# Shema.net
KiCad netlist of a schematic drawn in Altium Designer
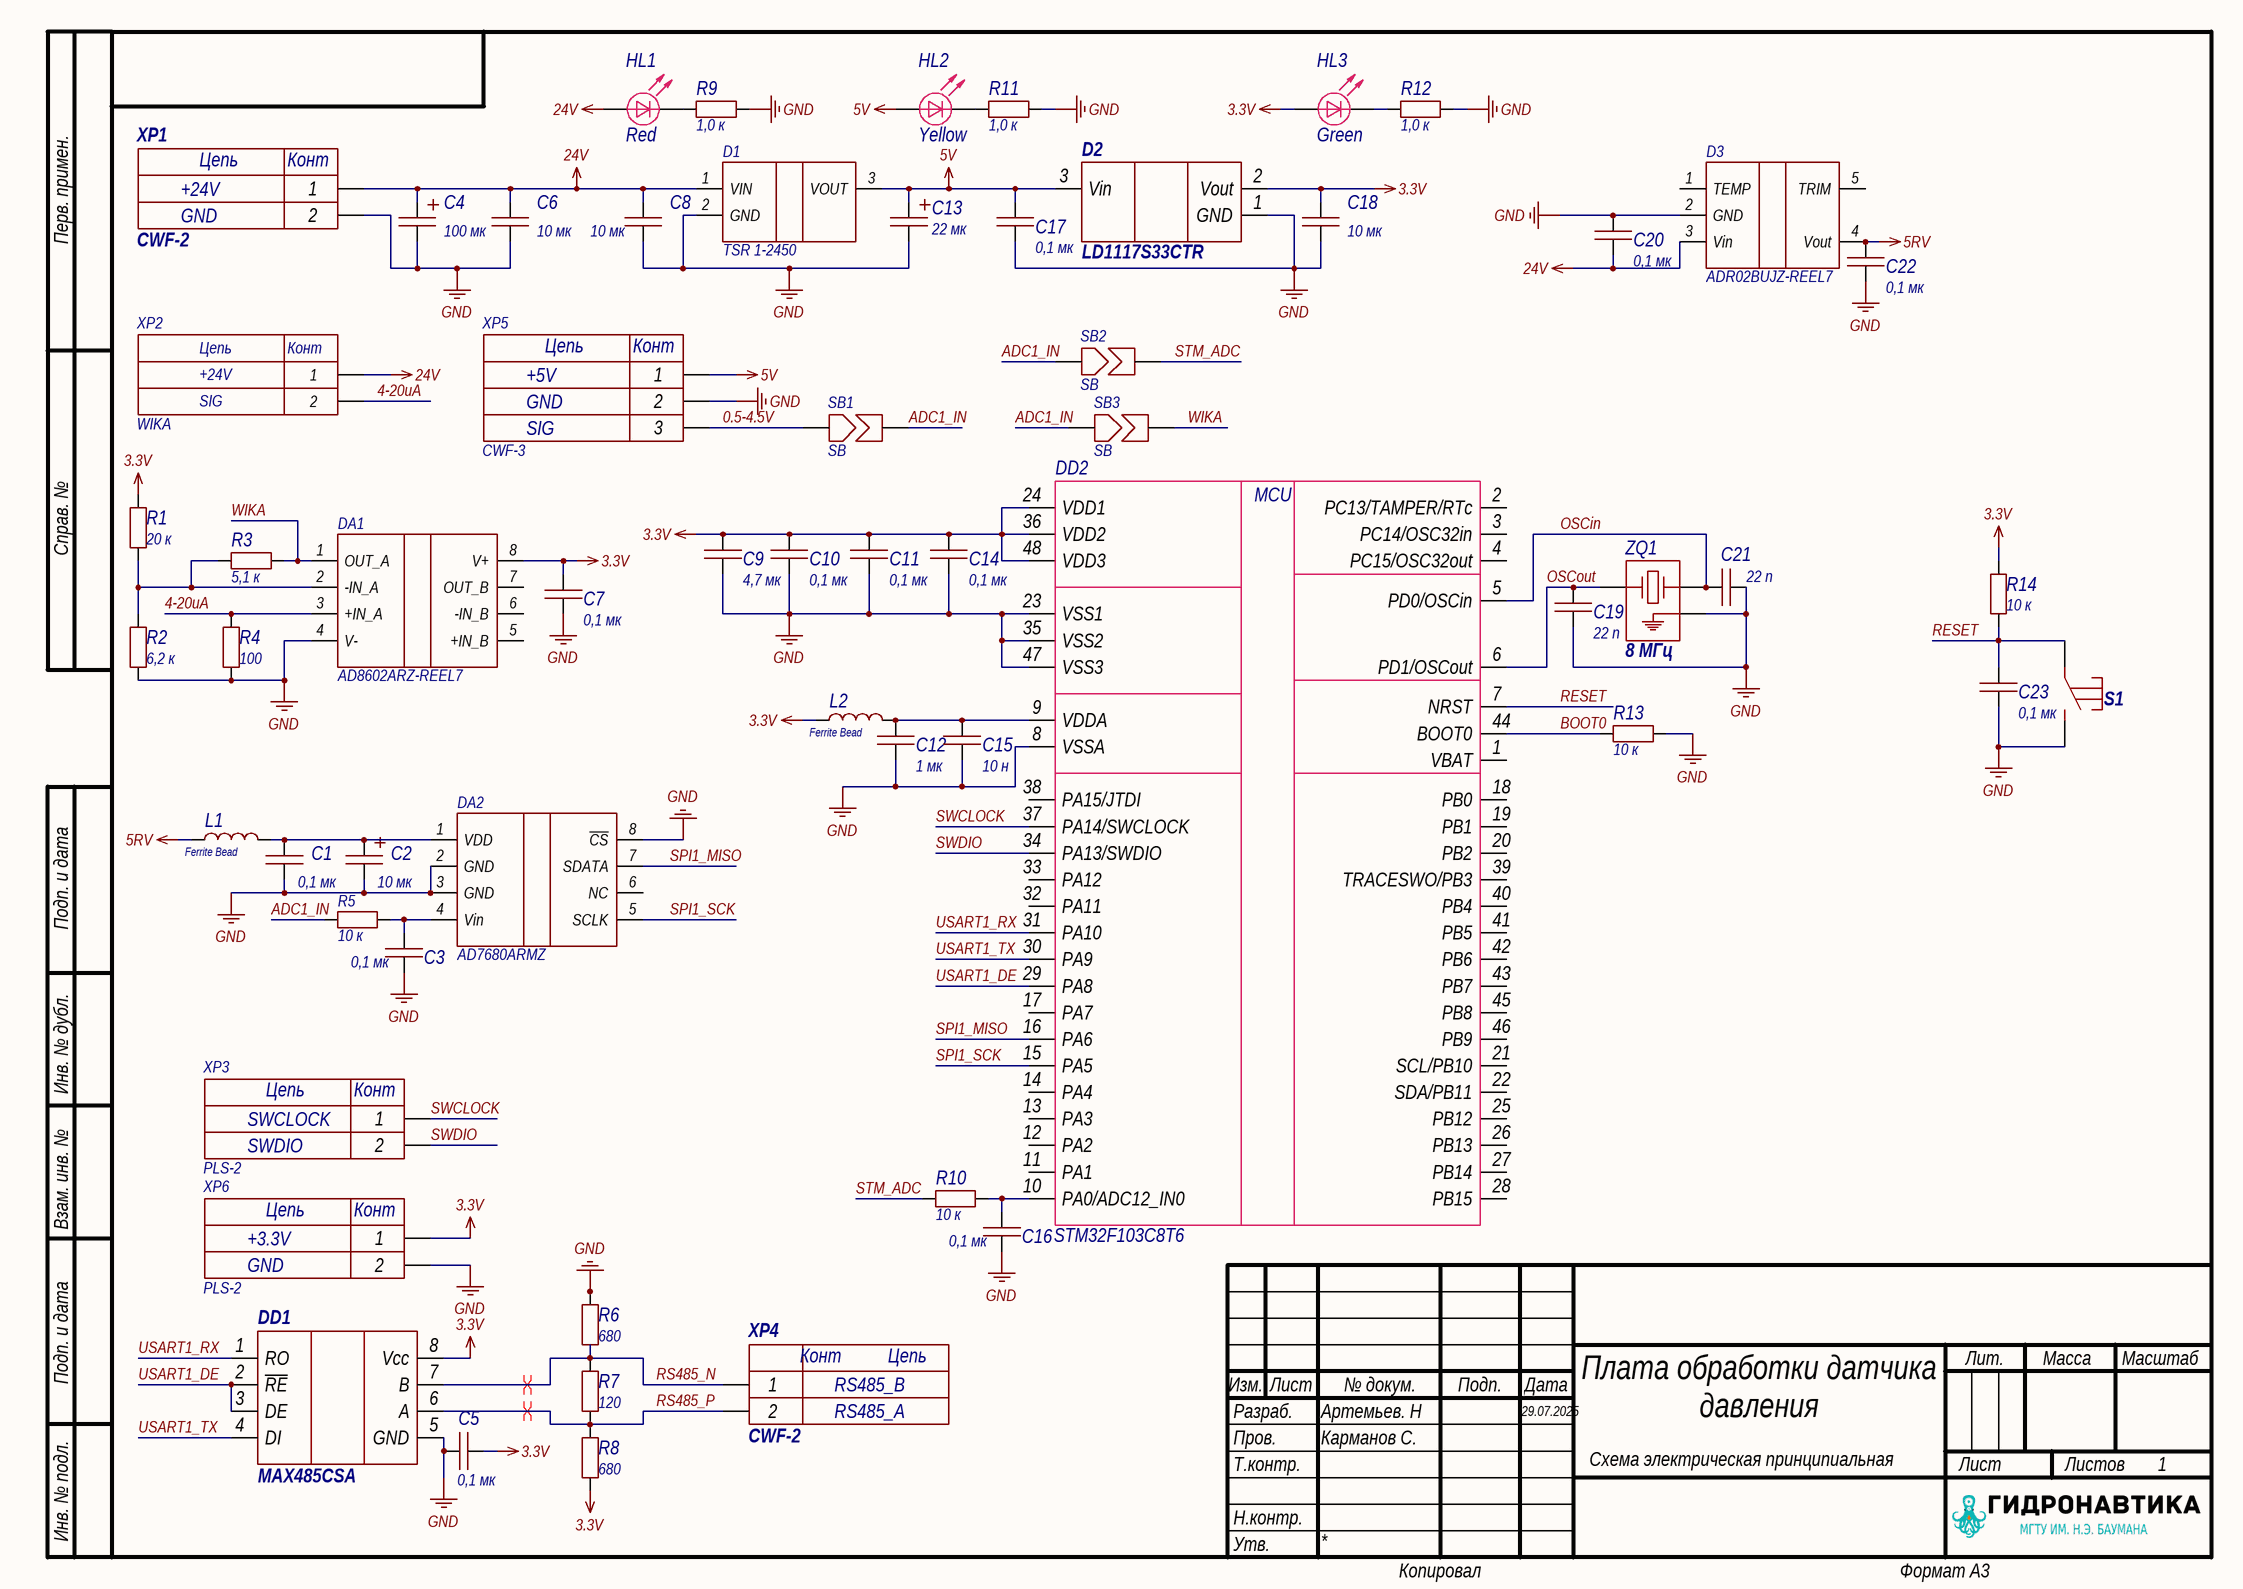
[diagram p0: Shema.SchDoc]

(export (version "E")
  (design (tool "Eeschema 10.0.6"))
  (components
    (comp (ref "C1")
      (value "0,1 мк")
      (footprint "0603C")
      (description "Конденсатор")
      (fields (field (name "PART NUMBER") "Capacitor_0,1u_10_50V_X7R_0603C") (field (name "TOLERANCE") "0,1"))
      (libsource (lib "Hydrolib") (part "Capacitor"))
    )
    (comp (ref "C2")
      (value "10 мк")
      (footprint "TC_A")
      (description "Танталовый конденсатор")
      (fields (field (name "PART NUMBER") "Capacitor_10u_10_50V_TC_A") (field (name "TOLERANCE") "0,1"))
      (libsource (lib "Hydrolib") (part "Capacitor_polar"))
    )
    (comp (ref "C3")
      (value "0,1 мк")
      (footprint "0603C")
      (description "Конденсатор")
      (fields (field (name "PART NUMBER") "Capacitor_0,1u_10_50V_X7R_0603C") (field (name "TOLERANCE") "0,1"))
      (libsource (lib "Hydrolib") (part "Capacitor"))
    )
    (comp (ref "C4")
      (value "100 мк")
      (footprint "TC_A")
      (description "Танталовый конденсатор")
      (fields (field (name "PART NUMBER") "Capacitor_100u_10_50V_TC_A") (field (name "TOLERANCE") "0,1"))
      (libsource (lib "Hydrolib") (part "Capacitor_polar"))
    )
    (comp (ref "C5")
      (value "0,1 мк")
      (footprint "0603C")
      (description "Конденсатор")
      (fields (field (name "PART NUMBER") "Capacitor_0,1u_10_50V_X7R_0603C") (field (name "TOLERANCE") "0,1"))
      (libsource (lib "Hydrolib") (part "Capacitor"))
    )
    (comp (ref "C6")
      (value "10 мк")
      (footprint "1210C")
      (description "Конденсатор")
      (fields (field (name "PART NUMBER") "Capacitor_10u_10_35V_X7R_1210C") (field (name "TOLERANCE") "0,1"))
      (libsource (lib "Hydrolib") (part "Capacitor"))
    )
    (comp (ref "C7")
      (value "0,1 мк")
      (footprint "0603C")
      (description "Конденсатор")
      (fields (field (name "PART NUMBER") "Capacitor_0,1u_10_50V_X7R_0603C") (field (name "TOLERANCE") "0,1"))
      (libsource (lib "Hydrolib") (part "Capacitor"))
    )
    (comp (ref "C8")
      (value "10 мк")
      (footprint "1210C")
      (description "Конденсатор")
      (fields (field (name "PART NUMBER") "Capacitor_10u_10_35V_X7R_1210C") (field (name "TOLERANCE") "0,1"))
      (libsource (lib "Hydrolib") (part "Capacitor"))
    )
    (comp (ref "C9")
      (value "4,7 мк")
      (footprint "1206C")
      (description "Конденсатор")
      (fields (field (name "PART NUMBER") "Capacitor_4,7u_10_50V_X7R_1206C") (field (name "TOLERANCE") "0,1"))
      (libsource (lib "Hydrolib") (part "Capacitor"))
    )
    (comp (ref "C10")
      (value "0,1 мк")
      (footprint "0603C")
      (description "Конденсатор")
      (fields (field (name "PART NUMBER") "Capacitor_0,1u_10_50V_X7R_0603C") (field (name "TOLERANCE") "0,1"))
      (libsource (lib "Hydrolib") (part "Capacitor"))
    )
    (comp (ref "C11")
      (value "0,1 мк")
      (footprint "0603C")
      (description "Конденсатор")
      (fields (field (name "PART NUMBER") "Capacitor_0,1u_10_50V_X7R_0603C") (field (name "TOLERANCE") "0,1"))
      (libsource (lib "Hydrolib") (part "Capacitor"))
    )
    (comp (ref "C12")
      (value "1 мк")
      (footprint "0603C")
      (description "Конденсатор")
      (fields (field (name "PART NUMBER") "Capacitor_1u_10_50V_X7R_0603C") (field (name "TOLERANCE") "0,1"))
      (libsource (lib "Hydrolib") (part "Capacitor"))
    )
    (comp (ref "C13")
      (value "22 мк")
      (footprint "TC_A")
      (description "Танталовый конденсатор")
      (fields (field (name "PART NUMBER") "Capacitor_22u_10_50V_TC_A") (field (name "TOLERANCE") "0,1"))
      (libsource (lib "Hydrolib") (part "Capacitor_polar"))
    )
    (comp (ref "C14")
      (value "0,1 мк")
      (footprint "0603C")
      (description "Конденсатор")
      (fields (field (name "PART NUMBER") "Capacitor_0,1u_10_50V_X7R_0603C") (field (name "TOLERANCE") "0,1"))
      (libsource (lib "Hydrolib") (part "Capacitor"))
    )
    (comp (ref "C15")
      (value "10 н")
      (footprint "0603C")
      (description "Конденсатор")
      (fields (field (name "PART NUMBER") "Capacitor_10n_10_50V_X7R_0603C") (field (name "TOLERANCE") "0,1"))
      (libsource (lib "Hydrolib") (part "Capacitor"))
    )
    (comp (ref "C16")
      (value "0,1 мк")
      (footprint "0603C")
      (description "Конденсатор")
      (fields (field (name "PART NUMBER") "Capacitor_0,1u_10_50V_X7R_0603C") (field (name "TOLERANCE") "0,1"))
      (libsource (lib "Hydrolib") (part "Capacitor"))
    )
    (comp (ref "C17")
      (value "0,1 мк")
      (footprint "0603C")
      (description "Конденсатор")
      (fields (field (name "PART NUMBER") "Capacitor_0,1u_10_50V_X7R_0603C") (field (name "TOLERANCE") "0,1"))
      (libsource (lib "Hydrolib") (part "Capacitor"))
    )
    (comp (ref "C18")
      (value "10 мк")
      (footprint "1210C")
      (description "Конденсатор")
      (fields (field (name "PART NUMBER") "Capacitor_10u_10_35V_X7R_1210C") (field (name "TOLERANCE") "0,1"))
      (libsource (lib "Hydrolib") (part "Capacitor"))
    )
    (comp (ref "C19")
      (value "22 п")
      (footprint "0603C")
      (description "Конденсатор")
      (fields (field (name "PART NUMBER") "Capacitor_22p_5_50V_X7R_0603C") (field (name "TOLERANCE") "0,05"))
      (libsource (lib "Hydrolib") (part "Capacitor"))
    )
    (comp (ref "C20")
      (value "0,1 мк")
      (footprint "0603C")
      (description "Конденсатор")
      (fields (field (name "PART NUMBER") "Capacitor_0,1u_10_50V_X7R_0603C") (field (name "TOLERANCE") "0,1"))
      (libsource (lib "Hydrolib") (part "Capacitor"))
    )
    (comp (ref "C21")
      (value "22 п")
      (footprint "0603C")
      (description "Конденсатор")
      (fields (field (name "PART NUMBER") "Capacitor_22p_5_50V_X7R_0603C") (field (name "TOLERANCE") "0,05"))
      (libsource (lib "Hydrolib") (part "Capacitor"))
    )
    (comp (ref "C22")
      (value "0,1 мк")
      (footprint "0603C")
      (description "Конденсатор")
      (fields (field (name "PART NUMBER") "Capacitor_0,1u_10_50V_X7R_0603C") (field (name "TOLERANCE") "0,1"))
      (libsource (lib "Hydrolib") (part "Capacitor"))
    )
    (comp (ref "C23")
      (value "0,1 мк")
      (footprint "0603C")
      (description "Конденсатор")
      (fields (field (name "PART NUMBER") "Capacitor_0,1u_10_50V_X7R_0603C") (field (name "TOLERANCE") "0,1"))
      (libsource (lib "Hydrolib") (part "Capacitor"))
    )
    (comp (ref "D1")
      (value "TSR 1-2450")
      (footprint "SIP3")
      (description "DC/DC преобразователь, 5Вт, вход 6.5-36В, выход 5В/ 1А")
      (libsource (lib "Hydrolib") (part "TSR 1-2450"))
    )
    (comp (ref "D2")
      (value "LD1117S33CTR")
      (footprint "SOT223")
      (description "Линейный стабилизатор напряжения")
      (libsource (lib "Hydrolib") (part "LD1117S33CTR"))
    )
    (comp (ref "D3")
      (value "ADR02BUJZ-REEL7")
      (footprint "SOT23-5")
      (description "Источник опорного напряжения, 5 В")
      (libsource (lib "Hydrolib") (part "ADR02BUJZ-REEL7"))
    )
    (comp (ref "DA1")
      (value "AD8602ARZ-REEL7")
      (footprint "SOIC-8")
      (description "2-х канальный прецизионный, широкополосный операционный усилитель с однополярным питанием")
      (libsource (lib "Hydrolib") (part "AD8602"))
    )
    (comp (ref "DA2")
      (value "AD7680ARMZ")
      (footprint "MSOP-8")
      (description "16-бит АЦП, SAR, 100Квыборок/с")
      (libsource (lib "Hydrolib") (part "AD7680ARMZ"))
    )
    (comp (ref "DD1")
      (value "MAX485CSA")
      (footprint "SOIC-8")
      (description "RS-485 приёмопередатчик")
      (libsource (lib "Hydrolib") (part "MAX485CSA"))
    )
    (comp (ref "DD2")
      (value "STM32F103C8T6")
      (footprint "LQFP48")
      (description "Микроконтроллер")
      (fields (field (name "MANUFACTURER") "ST Microelectronics") (field (name "VALUE1") "MCU"))
      (libsource (lib "Hydrolib") (part "STM32F103C8T6"))
    )
    (comp (ref "HL1")
      (value "LED")
      (footprint "0805D")
      (description "Светодиод")
      (fields (field (name "COLOR") "Red"))
      (libsource (lib "Hydrolib") (part "LED"))
    )
    (comp (ref "HL2")
      (value "LED")
      (footprint "0805D")
      (description "Светодиод")
      (fields (field (name "COLOR") "Yellow"))
      (libsource (lib "Hydrolib") (part "LED"))
    )
    (comp (ref "HL3")
      (value "LED")
      (footprint "0805D")
      (description "Светодиод")
      (fields (field (name "COLOR") "Green"))
      (libsource (lib "Hydrolib") (part "LED"))
    )
    (comp (ref "L1")
      (value "Ferrite Bead")
      (footprint "0603L")
      (fields (field (name "PART NUMBER") "Inductance"))
      (libsource (lib "Hydrolib") (part "Inductance"))
    )
    (comp (ref "L2")
      (value "Ferrite Bead")
      (footprint "0603L")
      (fields (field (name "PART NUMBER") "Inductance"))
      (libsource (lib "Hydrolib") (part "Inductance"))
    )
    (comp (ref "R1")
      (value "20 к")
      (footprint "0603R")
      (description "Резистор номиналом 20 кОм и точностью 1%")
      (fields (field (name "PART NUMBER") "Resistor_20k_1_0603") (field (name "TOLERANCE") "1%"))
      (libsource (lib "") (part "Resistor_1"))
    )
    (comp (ref "R2")
      (value "6,2 к")
      (footprint "0603R")
      (description "Резистор номиналом 6,2 кОм и точностью 1%")
      (fields (field (name "PART NUMBER") "Resistor_6.2k_1_0603") (field (name "TOLERANCE") "1%"))
      (libsource (lib "") (part "Resistor_1"))
    )
    (comp (ref "R3")
      (value "5,1 к")
      (footprint "0603R")
      (description "Резистор номиналом 5,1 кОм и точностью 1%")
      (fields (field (name "PART NUMBER") "Resistor_5.1k_1_0603") (field (name "TOLERANCE") "1%"))
      (libsource (lib "") (part "Resistor_2"))
    )
    (comp (ref "R4")
      (value "100")
      (footprint "0603R")
      (description "Резистор номиналом 100 Ом и точностью 1%")
      (fields (field (name "PART NUMBER") "Resistor_100_1_0603") (field (name "TOLERANCE") "1%"))
      (libsource (lib "Hydrolib") (part "Resistor"))
    )
    (comp (ref "R5")
      (value "10 к")
      (footprint "0603R")
      (description "Резистор номиналом 10 кОм и точностью 1%")
      (fields (field (name "PART NUMBER") "Resistor_10k_1_0603") (field (name "TOLERANCE") "1%"))
      (libsource (lib "") (part "Resistor_2"))
    )
    (comp (ref "R6")
      (value "680")
      (footprint "0603R")
      (description "Резистор номиналом 680 Ом и точностью 1%")
      (fields (field (name "PART NUMBER") "Resistor_680_1_0603") (field (name "TOLERANCE") "1%"))
      (libsource (lib "") (part "Resistor_1"))
    )
    (comp (ref "R7")
      (value "120")
      (footprint "0603R")
      (description "Резистор номиналом 120 Ом и точностью 1%")
      (fields (field (name "PART NUMBER") "Resistor_120_1_0603") (field (name "TOLERANCE") "1%"))
      (libsource (lib "") (part "Resistor_1"))
    )
    (comp (ref "R8")
      (value "680")
      (footprint "0603R")
      (description "Резистор номиналом 680 Ом и точностью 1%")
      (fields (field (name "PART NUMBER") "Resistor_680_1_0603") (field (name "TOLERANCE") "1%"))
      (libsource (lib "") (part "Resistor_1"))
    )
    (comp (ref "R9")
      (value "1,0 к")
      (footprint "0603R")
      (description "Резистор номиналом 1,0 кОм и точностью 1%")
      (fields (field (name "PART NUMBER") "Resistor_1.0k_1_0603") (field (name "TOLERANCE") "1%"))
      (libsource (lib "") (part "Resistor_2"))
    )
    (comp (ref "R10")
      (value "10 к")
      (footprint "0603R")
      (description "Резистор номиналом 10 кОм и точностью 1%")
      (fields (field (name "PART NUMBER") "Resistor_10k_1_0603") (field (name "TOLERANCE") "1%"))
      (libsource (lib "") (part "Resistor_2"))
    )
    (comp (ref "R11")
      (value "1,0 к")
      (footprint "0603R")
      (description "Резистор номиналом 1,0 кОм и точностью 1%")
      (fields (field (name "PART NUMBER") "Resistor_1.0k_1_0603") (field (name "TOLERANCE") "1%"))
      (libsource (lib "") (part "Resistor_2"))
    )
    (comp (ref "R12")
      (value "1,0 к")
      (footprint "0603R")
      (description "Резистор номиналом 1,0 кОм и точностью 1%")
      (fields (field (name "PART NUMBER") "Resistor_1.0k_1_0603") (field (name "TOLERANCE") "1%"))
      (libsource (lib "") (part "Resistor_2"))
    )
    (comp (ref "R13")
      (value "10 к")
      (footprint "0603R")
      (description "Резистор номиналом 10 кОм и точностью 1%")
      (fields (field (name "PART NUMBER") "Resistor_10k_1_0603") (field (name "TOLERANCE") "1%"))
      (libsource (lib "") (part "Resistor_2"))
    )
    (comp (ref "R14")
      (value "10 к")
      (footprint "0603R")
      (description "Резистор номиналом 10 кОм и точностью 1%")
      (fields (field (name "PART NUMBER") "Resistor_10k_1_0603") (field (name "TOLERANCE") "1%"))
      (libsource (lib "Hydrolib") (part "Resistor"))
    )
    (comp (ref "S1")
      (value "Tact_button")
      (footprint "Button_SMD_10mm")
      (description "Тактовая кнопка")
      (libsource (lib "Hydrolib") (part "Tact_button"))
    )
    (comp (ref "SB1")
      (value "SB")
      (footprint "0805SB")
      (description "Solder bridge, мост припоя, запаиваемая перемычка, net tie, jumper")
      (libsource (lib "Hydrolib") (part "SB"))
    )
    (comp (ref "SB2")
      (value "SB")
      (footprint "0805SB")
      (description "Solder bridge, мост припоя, запаиваемая перемычка, net tie, jumper")
      (libsource (lib "Hydrolib") (part "SB"))
    )
    (comp (ref "SB3")
      (value "SB")
      (footprint "0805SB")
      (description "Solder bridge, мост припоя, запаиваемая перемычка, net tie, jumper")
      (libsource (lib "Hydrolib") (part "SB"))
    )
    (comp (ref "XP1")
      (value "CWF-2")
      (footprint "CWF-2")
      (description "2-пиновый разъем с ключом")
      (fields (field (name "VALUE2") "GND") (field (name "VALUE1") "+24V"))
      (libsource (lib "Hydrolib") (part "Conn_2pin"))
    )
    (comp (ref "XP2") (value "WIKA") (footprint "WIKA_PCB") (libsource (lib "Hydrolib") (part "WIKA")))
    (comp (ref "XP3")
      (value "PLS-2")
      (footprint "PLS2")
      (description "Гребенка 2 пина")
      (fields (field (name "VALUE2") "SWDIO") (field (name "VALUE1") "SWCLOCK"))
      (libsource (lib "Hydrolib") (part "Conn_2pin"))
    )
    (comp (ref "XP4")
      (value "CWF-2")
      (footprint "CWF-2")
      (description "2-пиновый разъем с ключом")
      (fields (field (name "VALUE2") "RS485_A") (field (name "VALUE1") "RS485_B"))
      (libsource (lib "Hydrolib") (part "Conn_2pin"))
    )
    (comp (ref "XP5")
      (value "CWF-3")
      (footprint "CWF-3")
      (description "3-пиновый разъем с ключом")
      (fields (field (name "VALUE3") "SIG") (field (name "VALUE2") "GND") (field (name "VALUE1") "+5V"))
      (libsource (lib "Hydrolib") (part "Conn_3pin"))
    )
    (comp (ref "XP6")
      (value "PLS-2")
      (footprint "PLS2")
      (description "Гребенка 2 пина")
      (fields (field (name "VALUE2") "GND") (field (name "VALUE1") "+3.3V"))
      (libsource (lib "Hydrolib") (part "Conn_2pin"))
    )
    (comp (ref "ZQ1")
      (value "8 МГц")
      (footprint "QSMD3.2x2.5")
      (description "Кварцевый резонатор с входом земли")
      (fields (field (name "PART NUMBER") "XTAL_GND"))
      (libsource (lib "Hydrolib") (part "XTAL_GND"))
    )
  )
  (nets
    (net (code "1") (name "/0.5-4.5V") (class "Default")
      (node (ref "SB1") (pin "1") (pinfunction "1_1") (pintype "passive"))
      (node (ref "XP5") (pin "3") (pinfunction "3_3") (pintype "passive"))
    )
    (net (code "2") (name "/4-20uA") (class "Default")
      (node (ref "DA1") (pin "3") (pinfunction "+IN_A_3") (pintype "passive"))
      (node (ref "R4") (pin "1") (pinfunction "1_1") (pintype "passive"))
      (node (ref "XP2") (pin "2") (pinfunction "2_2") (pintype "passive"))
    )
    (net (code "3") (name "/ADC1_IN") (class "Default")
      (node (ref "R5") (pin "1") (pinfunction "1_1") (pintype "passive"))
      (node (ref "SB1") (pin "2") (pinfunction "2_2") (pintype "passive"))
      (node (ref "SB2") (pin "1") (pinfunction "1_1") (pintype "passive"))
      (node (ref "SB3") (pin "1") (pinfunction "1_1") (pintype "passive"))
    )
    (net (code "4") (name "/BOOT0") (class "Default")
      (node (ref "DD2") (pin "44") (pinfunction "BOOT0_44") (pintype "passive"))
      (node (ref "R13") (pin "1") (pinfunction "1_1") (pintype "passive"))
    )
    (net (code "5") (name "/OSCin") (class "Default")
      (node (ref "C21") (pin "2") (pinfunction "2_2") (pintype "passive"))
      (node (ref "DD2") (pin "5") (pinfunction "PD0/OSCin_5") (pintype "passive"))
      (node (ref "ZQ1") (pin "2") (pinfunction "2_2") (pintype "passive"))
    )
    (net (code "6") (name "/OSCout") (class "Default")
      (node (ref "C19") (pin "1") (pinfunction "1_1") (pintype "passive"))
      (node (ref "DD2") (pin "6") (pinfunction "PD1/OSCout_6") (pintype "passive"))
      (node (ref "ZQ1") (pin "1") (pinfunction "1_1") (pintype "passive"))
    )
    (net (code "7") (name "/RESET") (class "Default")
      (node (ref "C23") (pin "1") (pinfunction "1_1") (pintype "passive"))
      (node (ref "DD2") (pin "7") (pinfunction "NRST_7") (pintype "passive"))
      (node (ref "R14") (pin "2") (pinfunction "2_2") (pintype "passive"))
      (node (ref "S1") (pin "1") (pinfunction "1_1") (pintype "passive"))
    )
    (net (code "8") (name "/RS485_N") (class "Default")
      (node (ref "DD1") (pin "7") (pinfunction "B_7") (pintype "passive"))
      (node (ref "R6") (pin "1") (pinfunction "1_1") (pintype "passive"))
      (node (ref "R7") (pin "2") (pinfunction "2_2") (pintype "passive"))
      (node (ref "XP4") (pin "1") (pinfunction "1_1") (pintype "passive"))
    )
    (net (code "9") (name "/RS485_P") (class "Default")
      (node (ref "DD1") (pin "6") (pinfunction "A_6") (pintype "passive"))
      (node (ref "R7") (pin "1") (pinfunction "1_1") (pintype "passive"))
      (node (ref "R8") (pin "2") (pinfunction "2_2") (pintype "passive"))
      (node (ref "XP4") (pin "2") (pinfunction "2_2") (pintype "passive"))
    )
    (net (code "10") (name "/SPI1_MISO") (class "Default")
      (node (ref "DA2") (pin "7") (pinfunction "SDATA_7") (pintype "passive"))
      (node (ref "DD2") (pin "16") (pinfunction "PA6_16") (pintype "passive"))
    )
    (net (code "11") (name "/SPI1_SCK") (class "Default")
      (node (ref "DA2") (pin "5") (pinfunction "SCLK_5") (pintype "passive"))
      (node (ref "DD2") (pin "15") (pinfunction "PA5_15") (pintype "passive"))
    )
    (net (code "12") (name "/STM_ADC") (class "Default")
      (node (ref "R10") (pin "1") (pinfunction "1_1") (pintype "passive"))
      (node (ref "SB2") (pin "2") (pinfunction "2_2") (pintype "passive"))
    )
    (net (code "13") (name "/SWCLOCK") (class "Default")
      (node (ref "DD2") (pin "37") (pinfunction "PA14/SWCLOCK_37") (pintype "passive"))
      (node (ref "XP3") (pin "1") (pinfunction "1_1") (pintype "passive"))
    )
    (net (code "14") (name "/SWDIO") (class "Default")
      (node (ref "DD2") (pin "34") (pinfunction "PA13/SWDIO_34") (pintype "passive"))
      (node (ref "XP3") (pin "2") (pinfunction "2_2") (pintype "passive"))
    )
    (net (code "15") (name "/USART1_DE") (class "Default")
      (node (ref "DD1") (pin "2") (pinfunction "RE_2") (pintype "passive"))
      (node (ref "DD1") (pin "3") (pinfunction "DE_3") (pintype "passive"))
      (node (ref "DD2") (pin "29") (pinfunction "PA8_29") (pintype "passive"))
    )
    (net (code "16") (name "/USART1_RX") (class "Default")
      (node (ref "DD1") (pin "1") (pinfunction "RO_1") (pintype "passive"))
      (node (ref "DD2") (pin "31") (pinfunction "PA10_31") (pintype "passive"))
    )
    (net (code "17") (name "/USART1_TX") (class "Default")
      (node (ref "DD1") (pin "4") (pinfunction "DI_4") (pintype "passive"))
      (node (ref "DD2") (pin "30") (pinfunction "PA9_30") (pintype "passive"))
    )
    (net (code "18") (name "/WIKA") (class "Default")
      (node (ref "DA1") (pin "1") (pinfunction "OUT_A_1") (pintype "passive"))
      (node (ref "R3") (pin "2") (pinfunction "2_2") (pintype "passive"))
      (node (ref "SB3") (pin "2") (pinfunction "2_2") (pintype "passive"))
    )
    (net (code "19") (name "3.3V") (class "Default")
      (node (ref "C10") (pin "2") (pinfunction "2_2") (pintype "passive"))
      (node (ref "C11") (pin "2") (pinfunction "2_2") (pintype "passive"))
      (node (ref "C14") (pin "2") (pinfunction "2_2") (pintype "passive"))
      (node (ref "C18") (pin "2") (pinfunction "2_2") (pintype "passive"))
      (node (ref "C5") (pin "2") (pinfunction "2_2") (pintype "passive"))
      (node (ref "C7") (pin "2") (pinfunction "2_2") (pintype "passive"))
      (node (ref "C9") (pin "2") (pinfunction "2_2") (pintype "passive"))
      (node (ref "D2") (pin "2") (pinfunction "Vout_2") (pintype "passive"))
      (node (ref "DA1") (pin "8") (pinfunction "V+_8") (pintype "passive"))
      (node (ref "DD1") (pin "8") (pinfunction "Vcc_8") (pintype "passive"))
      (node (ref "DD2") (pin "24") (pinfunction "VDD1_24") (pintype "passive"))
      (node (ref "DD2") (pin "36") (pinfunction "VDD2_36") (pintype "passive"))
      (node (ref "DD2") (pin "48") (pinfunction "VDD3_48") (pintype "passive"))
      (node (ref "HL3") (pin "1") (pinfunction "1_1") (pintype "passive"))
      (node (ref "L2") (pin "1") (pinfunction "1_1") (pintype "passive"))
      (node (ref "R1") (pin "2") (pinfunction "2_2") (pintype "passive"))
      (node (ref "R14") (pin "1") (pinfunction "1_1") (pintype "passive"))
      (node (ref "R8") (pin "1") (pinfunction "1_1") (pintype "passive"))
      (node (ref "XP6") (pin "1") (pinfunction "1_1") (pintype "passive"))
    )
    (net (code "20") (name "5RV") (class "Default")
      (node (ref "C22") (pin "2") (pinfunction "2_2") (pintype "passive"))
      (node (ref "D3") (pin "4") (pinfunction "Vout_4") (pintype "passive"))
      (node (ref "L1") (pin "1") (pinfunction "1_1") (pintype "passive"))
    )
    (net (code "21") (name "5V") (class "Default")
      (node (ref "C13") (pin "1") (pinfunction "1_1") (pintype "passive"))
      (node (ref "C17") (pin "2") (pinfunction "2_2") (pintype "passive"))
      (node (ref "D1") (pin "3") (pinfunction "VOUT_3") (pintype "passive"))
      (node (ref "D2") (pin "3") (pinfunction "Vin_3") (pintype "passive"))
      (node (ref "HL2") (pin "1") (pinfunction "1_1") (pintype "passive"))
      (node (ref "XP5") (pin "1") (pinfunction "1_1") (pintype "passive"))
    )
    (net (code "22") (name "24V") (class "Default")
      (node (ref "C20") (pin "1") (pinfunction "1_1") (pintype "passive"))
      (node (ref "C4") (pin "1") (pinfunction "1_1") (pintype "passive"))
      (node (ref "C6") (pin "2") (pinfunction "2_2") (pintype "passive"))
      (node (ref "C8") (pin "2") (pinfunction "2_2") (pintype "passive"))
      (node (ref "D1") (pin "1") (pinfunction "VIN_1") (pintype "passive"))
      (node (ref "D3") (pin "3") (pinfunction "Vin_3") (pintype "passive"))
      (node (ref "HL1") (pin "1") (pinfunction "1_1") (pintype "passive"))
      (node (ref "XP1") (pin "1") (pinfunction "1_1") (pintype "passive"))
      (node (ref "XP2") (pin "1") (pinfunction "1_1") (pintype "passive"))
    )
    (net (code "23") (name "GND") (class "Default")
      (node (ref "C1") (pin "1") (pinfunction "1_1") (pintype "passive"))
      (node (ref "C10") (pin "1") (pinfunction "1_1") (pintype "passive"))
      (node (ref "C11") (pin "1") (pinfunction "1_1") (pintype "passive"))
      (node (ref "C12") (pin "1") (pinfunction "1_1") (pintype "passive"))
      (node (ref "C13") (pin "2") (pinfunction "2_2") (pintype "passive"))
      (node (ref "C14") (pin "1") (pinfunction "1_1") (pintype "passive"))
      (node (ref "C15") (pin "1") (pinfunction "1_1") (pintype "passive"))
      (node (ref "C16") (pin "1") (pinfunction "1_1") (pintype "passive"))
      (node (ref "C17") (pin "1") (pinfunction "1_1") (pintype "passive"))
      (node (ref "C18") (pin "1") (pinfunction "1_1") (pintype "passive"))
      (node (ref "C19") (pin "2") (pinfunction "2_2") (pintype "passive"))
      (node (ref "C2") (pin "2") (pinfunction "2_2") (pintype "passive"))
      (node (ref "C20") (pin "2") (pinfunction "2_2") (pintype "passive"))
      (node (ref "C21") (pin "1") (pinfunction "1_1") (pintype "passive"))
      (node (ref "C22") (pin "1") (pinfunction "1_1") (pintype "passive"))
      (node (ref "C23") (pin "2") (pinfunction "2_2") (pintype "passive"))
      (node (ref "C3") (pin "1") (pinfunction "1_1") (pintype "passive"))
      (node (ref "C4") (pin "2") (pinfunction "2_2") (pintype "passive"))
      (node (ref "C5") (pin "1") (pinfunction "1_1") (pintype "passive"))
      (node (ref "C6") (pin "1") (pinfunction "1_1") (pintype "passive"))
      (node (ref "C7") (pin "1") (pinfunction "1_1") (pintype "passive"))
      (node (ref "C8") (pin "1") (pinfunction "1_1") (pintype "passive"))
      (node (ref "C9") (pin "1") (pinfunction "1_1") (pintype "passive"))
      (node (ref "D1") (pin "2") (pinfunction "GND_2") (pintype "passive"))
      (node (ref "D2") (pin "1") (pinfunction "GND_1") (pintype "passive"))
      (node (ref "D3") (pin "2") (pinfunction "GND_2") (pintype "passive"))
      (node (ref "DA1") (pin "4") (pinfunction "V-_4") (pintype "passive"))
      (node (ref "DA2") (pin "2") (pinfunction "GND_2") (pintype "passive"))
      (node (ref "DA2") (pin "3") (pinfunction "GND_3") (pintype "passive"))
      (node (ref "DA2") (pin "8") (pinfunction "~{CS}_8") (pintype "passive"))
      (node (ref "DD1") (pin "5") (pinfunction "GND_5") (pintype "passive"))
      (node (ref "DD2") (pin "23") (pinfunction "VSS1_23") (pintype "passive"))
      (node (ref "DD2") (pin "35") (pinfunction "VSS2_35") (pintype "passive"))
      (node (ref "DD2") (pin "47") (pinfunction "VSS3_47") (pintype "passive"))
      (node (ref "DD2") (pin "8") (pinfunction "VSSA_8") (pintype "passive"))
      (node (ref "R11") (pin "2") (pinfunction "2_2") (pintype "passive"))
      (node (ref "R12") (pin "2") (pinfunction "2_2") (pintype "passive"))
      (node (ref "R13") (pin "2") (pinfunction "2_2") (pintype "passive"))
      (node (ref "R2") (pin "1") (pinfunction "1_1") (pintype "passive"))
      (node (ref "R4") (pin "2") (pinfunction "2_2") (pintype "passive"))
      (node (ref "R6") (pin "2") (pinfunction "2_2") (pintype "passive"))
      (node (ref "R9") (pin "2") (pinfunction "2_2") (pintype "passive"))
      (node (ref "S1") (pin "2") (pinfunction "2_2") (pintype "passive"))
      (node (ref "XP1") (pin "2") (pinfunction "2_2") (pintype "passive"))
      (node (ref "XP5") (pin "2") (pinfunction "2_2") (pintype "passive"))
      (node (ref "XP6") (pin "2") (pinfunction "2_2") (pintype "passive"))
      (node (ref "ZQ1") (pin "3") (pinfunction "3_3") (pintype "passive"))
    )
    (net (code "24") (name "Net-(DA1--IN_A)") (class "Default")
      (node (ref "DA1") (pin "2") (pinfunction "-IN_A_2") (pintype "passive"))
      (node (ref "R1") (pin "1") (pinfunction "1_1") (pintype "passive"))
      (node (ref "R2") (pin "2") (pinfunction "2_2") (pintype "passive"))
      (node (ref "R3") (pin "1") (pinfunction "1_1") (pintype "passive"))
    )
    (net (code "25") (name "Net-(DA2-VDD)") (class "Default")
      (node (ref "C1") (pin "2") (pinfunction "2_2") (pintype "passive"))
      (node (ref "C2") (pin "1") (pinfunction "1_1") (pintype "passive"))
      (node (ref "DA2") (pin "1") (pinfunction "VDD_1") (pintype "passive"))
      (node (ref "L1") (pin "2") (pinfunction "2_2") (pintype "passive"))
    )
    (net (code "26") (name "Net-(DA2-Vin)") (class "Default")
      (node (ref "C3") (pin "2") (pinfunction "2_2") (pintype "passive"))
      (node (ref "DA2") (pin "4") (pinfunction "Vin_4") (pintype "passive"))
      (node (ref "R5") (pin "2") (pinfunction "2_2") (pintype "passive"))
    )
    (net (code "27") (name "Net-(DD2-PA0{slash}ADC12_IN0)") (class "Default")
      (node (ref "C16") (pin "2") (pinfunction "2_2") (pintype "passive"))
      (node (ref "DD2") (pin "10") (pinfunction "PA0/ADC12_IN0_10") (pintype "passive"))
      (node (ref "R10") (pin "2") (pinfunction "2_2") (pintype "passive"))
    )
    (net (code "28") (name "Net-(DD2-VDDA)") (class "Default")
      (node (ref "C12") (pin "2") (pinfunction "2_2") (pintype "passive"))
      (node (ref "C15") (pin "2") (pinfunction "2_2") (pintype "passive"))
      (node (ref "DD2") (pin "9") (pinfunction "VDDA_9") (pintype "passive"))
      (node (ref "L2") (pin "2") (pinfunction "2_2") (pintype "passive"))
    )
    (net (code "29") (name "Net-(HL1-Pad2)") (class "Default")
      (node (ref "HL1") (pin "2") (pinfunction "2_2") (pintype "passive"))
      (node (ref "R9") (pin "1") (pinfunction "1_1") (pintype "passive"))
    )
    (net (code "30") (name "Net-(HL2-Pad2)") (class "Default")
      (node (ref "HL2") (pin "2") (pinfunction "2_2") (pintype "passive"))
      (node (ref "R11") (pin "1") (pinfunction "1_1") (pintype "passive"))
    )
    (net (code "31") (name "Net-(HL3-Pad2)") (class "Default")
      (node (ref "HL3") (pin "2") (pinfunction "2_2") (pintype "passive"))
      (node (ref "R12") (pin "1") (pinfunction "1_1") (pintype "passive"))
    )
    (net (code "32") (name "unconnected-(D3-TEMP-Pad1)") (class "Default")
      (node (ref "D3") (pin "1") (pinfunction "TEMP_1") (pintype "passive"))
    )
    (net (code "33") (name "unconnected-(D3-TRIM-Pad5)") (class "Default")
      (node (ref "D3") (pin "5") (pinfunction "TRIM_5") (pintype "passive"))
    )
    (net (code "34") (name "unconnected-(DA1-+IN_B-Pad5)") (class "Default")
      (node (ref "DA1") (pin "5") (pinfunction "+IN_B_5") (pintype "passive"))
    )
    (net (code "35") (name "unconnected-(DA1--IN_B-Pad6)") (class "Default")
      (node (ref "DA1") (pin "6") (pinfunction "-IN_B_6") (pintype "passive"))
    )
    (net (code "36") (name "unconnected-(DA1-OUT_B-Pad7)") (class "Default")
      (node (ref "DA1") (pin "7") (pinfunction "OUT_B_7") (pintype "passive"))
    )
    (net (code "37") (name "unconnected-(DA2-NC-Pad6)") (class "Default")
      (node (ref "DA2") (pin "6") (pinfunction "NC_6") (pintype "passive"))
    )
    (net (code "38") (name "unconnected-(DD2-PA1-Pad11)") (class "Default")
      (node (ref "DD2") (pin "11") (pinfunction "PA1_11") (pintype "passive"))
    )
    (net (code "39") (name "unconnected-(DD2-PA2-Pad12)") (class "Default")
      (node (ref "DD2") (pin "12") (pinfunction "PA2_12") (pintype "passive"))
    )
    (net (code "40") (name "unconnected-(DD2-PA3-Pad13)") (class "Default")
      (node (ref "DD2") (pin "13") (pinfunction "PA3_13") (pintype "passive"))
    )
    (net (code "41") (name "unconnected-(DD2-PA4-Pad14)") (class "Default")
      (node (ref "DD2") (pin "14") (pinfunction "PA4_14") (pintype "passive"))
    )
    (net (code "42") (name "unconnected-(DD2-PA7-Pad17)") (class "Default")
      (node (ref "DD2") (pin "17") (pinfunction "PA7_17") (pintype "passive"))
    )
    (net (code "43") (name "unconnected-(DD2-PA11-Pad32)") (class "Default")
      (node (ref "DD2") (pin "32") (pinfunction "PA11_32") (pintype "passive"))
    )
    (net (code "44") (name "unconnected-(DD2-PA12-Pad33)") (class "Default")
      (node (ref "DD2") (pin "33") (pinfunction "PA12_33") (pintype "passive"))
    )
    (net (code "45") (name "unconnected-(DD2-PA15{slash}JTDI-Pad38)") (class "Default")
      (node (ref "DD2") (pin "38") (pinfunction "PA15/JTDI_38") (pintype "passive"))
    )
    (net (code "46") (name "unconnected-(DD2-PB0-Pad18)") (class "Default")
      (node (ref "DD2") (pin "18") (pinfunction "PB0_18") (pintype "passive"))
    )
    (net (code "47") (name "unconnected-(DD2-PB1-Pad19)") (class "Default")
      (node (ref "DD2") (pin "19") (pinfunction "PB1_19") (pintype "passive"))
    )
    (net (code "48") (name "unconnected-(DD2-PB2-Pad20)") (class "Default")
      (node (ref "DD2") (pin "20") (pinfunction "PB2_20") (pintype "passive"))
    )
    (net (code "49") (name "unconnected-(DD2-PB4-Pad40)") (class "Default")
      (node (ref "DD2") (pin "40") (pinfunction "PB4_40") (pintype "passive"))
    )
    (net (code "50") (name "unconnected-(DD2-PB5-Pad41)") (class "Default")
      (node (ref "DD2") (pin "41") (pinfunction "PB5_41") (pintype "passive"))
    )
    (net (code "51") (name "unconnected-(DD2-PB6-Pad42)") (class "Default")
      (node (ref "DD2") (pin "42") (pinfunction "PB6_42") (pintype "passive"))
    )
    (net (code "52") (name "unconnected-(DD2-PB7-Pad43)") (class "Default")
      (node (ref "DD2") (pin "43") (pinfunction "PB7_43") (pintype "passive"))
    )
    (net (code "53") (name "unconnected-(DD2-PB8-Pad45)") (class "Default")
      (node (ref "DD2") (pin "45") (pinfunction "PB8_45") (pintype "passive"))
    )
    (net (code "54") (name "unconnected-(DD2-PB9-Pad46)") (class "Default")
      (node (ref "DD2") (pin "46") (pinfunction "PB9_46") (pintype "passive"))
    )
    (net (code "55") (name "unconnected-(DD2-PB12-Pad25)") (class "Default")
      (node (ref "DD2") (pin "25") (pinfunction "PB12_25") (pintype "passive"))
    )
    (net (code "56") (name "unconnected-(DD2-PB13-Pad26)") (class "Default")
      (node (ref "DD2") (pin "26") (pinfunction "PB13_26") (pintype "passive"))
    )
    (net (code "57") (name "unconnected-(DD2-PB14-Pad27)") (class "Default")
      (node (ref "DD2") (pin "27") (pinfunction "PB14_27") (pintype "passive"))
    )
    (net (code "58") (name "unconnected-(DD2-PB15-Pad28)") (class "Default")
      (node (ref "DD2") (pin "28") (pinfunction "PB15_28") (pintype "passive"))
    )
    (net (code "59") (name "unconnected-(DD2-PC13{slash}TAMPER{slash}RTc-Pad2)") (class "Default")
      (node (ref "DD2") (pin "2") (pinfunction "PC13/TAMPER/RTc_2") (pintype "passive"))
    )
    (net (code "60") (name "unconnected-(DD2-PC14{slash}OSC32in-Pad3)") (class "Default")
      (node (ref "DD2") (pin "3") (pinfunction "PC14/OSC32in_3") (pintype "passive"))
    )
    (net (code "61") (name "unconnected-(DD2-PC15{slash}OSC32out-Pad4)") (class "Default")
      (node (ref "DD2") (pin "4") (pinfunction "PC15/OSC32out_4") (pintype "passive"))
    )
    (net (code "62") (name "unconnected-(DD2-SCL{slash}PB10-Pad21)") (class "Default")
      (node (ref "DD2") (pin "21") (pinfunction "SCL/PB10_21") (pintype "passive"))
    )
    (net (code "63") (name "unconnected-(DD2-SDA{slash}PB11-Pad22)") (class "Default")
      (node (ref "DD2") (pin "22") (pinfunction "SDA/PB11_22") (pintype "passive"))
    )
    (net (code "64") (name "unconnected-(DD2-TRACESWO{slash}PB3-Pad39)") (class "Default")
      (node (ref "DD2") (pin "39") (pinfunction "TRACESWO/PB3_39") (pintype "passive"))
    )
    (net (code "65") (name "unconnected-(DD2-VBAT-Pad1)") (class "Default")
      (node (ref "DD2") (pin "1") (pinfunction "VBAT_1") (pintype "passive"))
    )
  )
)
